# Display.net
KiCad netlist of a schematic drawn in Altium Designer
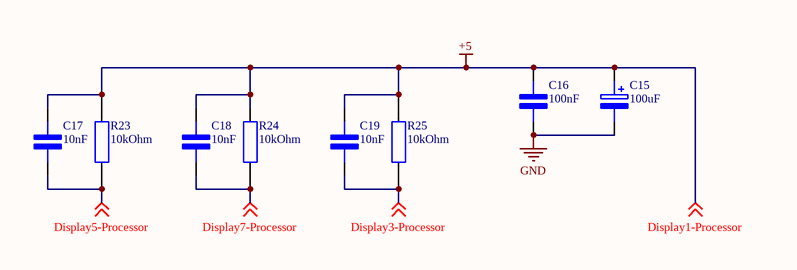
[diagram p0: Display.SchDoc]

(export (version "E")
  (design (tool "Eeschema 10.0.6"))
  (components
    (comp (ref "C15")
      (value "100uF")
      (footprint "PcbLib1:100uF capacitor")
      (description "Capacitor Polarised")
      (fields (field (name "MANUFACTURER_PART_NUMBER") "ESK107M050AG3EA"))
      (libsource (lib "Schlib1") (part "100uF"))
    )
    (comp (ref "C16")
      (value "100nF")
      (footprint "5mm lead spacing capacitor")
      (description "Capacitor")
      (fields (field (name "MANUFACTURER_PART_NUMBER") "UVR1H472MRD"))
      (libsource (lib "Schlib1") (part "100nF"))
    )
    (comp (ref "C17")
      (value "10nF")
      (footprint "5mm lead spacing capacitor")
      (description "Capacitor")
      (fields (field (name "MANUFACTURER_PART_NUMBER") "UVR1H472MRD"))
      (libsource (lib "Schlib1") (part "10nF"))
    )
    (comp (ref "C18")
      (value "10nF")
      (footprint "5mm lead spacing capacitor")
      (description "Capacitor")
      (fields (field (name "MANUFACTURER_PART_NUMBER") "UVR1H472MRD"))
      (libsource (lib "Schlib1") (part "10nF"))
    )
    (comp (ref "C19")
      (value "10nF")
      (footprint "5mm lead spacing capacitor")
      (description "Capacitor")
      (fields (field (name "MANUFACTURER_PART_NUMBER") "UVR1H472MRD"))
      (libsource (lib "Schlib1") (part "10nF"))
    )
    (comp (ref "R23")
      (value "10kOhm")
      (footprint "resistor")
      (description "Resistor")
      (fields (field (name "MANUFACTURER_PART_NUMBER") "CFR-25JT-52-10K"))
      (libsource (lib "Schlib1") (part "10kOhm"))
    )
    (comp (ref "R24")
      (value "10kOhm")
      (footprint "resistor")
      (description "Resistor")
      (fields (field (name "MANUFACTURER_PART_NUMBER") "CFR-25JT-52-10K"))
      (libsource (lib "Schlib1") (part "10kOhm"))
    )
    (comp (ref "R25")
      (value "10kOhm")
      (footprint "resistor")
      (description "Resistor")
      (fields (field (name "MANUFACTURER_PART_NUMBER") "CFR-25JT-52-10K"))
      (libsource (lib "Schlib1") (part "10kOhm"))
    )
  )
  (nets
    (net (code "1") (name "+5") (class "Default")
      (node (ref "C15") (pin "1") (pinfunction "+_1") (pintype "passive"))
      (node (ref "C16") (pin "2") (pinfunction "-_2") (pintype "passive"))
      (node (ref "C17") (pin "2") (pinfunction "-_2") (pintype "passive"))
      (node (ref "C18") (pin "2") (pinfunction "-_2") (pintype "passive"))
      (node (ref "C19") (pin "2") (pinfunction "-_2") (pintype "passive"))
      (node (ref "R23") (pin "2") (pinfunction "2_2") (pintype "passive"))
      (node (ref "R24") (pin "2") (pinfunction "2_2") (pintype "passive"))
      (node (ref "R25") (pin "2") (pinfunction "2_2") (pintype "passive"))
    )
    (net (code "2") (name "Display3-Processor") (class "Default")
      (node (ref "C19") (pin "1") (pinfunction "+_1") (pintype "passive"))
      (node (ref "R25") (pin "1") (pinfunction "1_1") (pintype "passive"))
    )
    (net (code "3") (name "Display5-Processor") (class "Default")
      (node (ref "C17") (pin "1") (pinfunction "+_1") (pintype "passive"))
      (node (ref "R23") (pin "1") (pinfunction "1_1") (pintype "passive"))
    )
    (net (code "4") (name "Display7-Processor") (class "Default")
      (node (ref "C18") (pin "1") (pinfunction "+_1") (pintype "passive"))
      (node (ref "R24") (pin "1") (pinfunction "1_1") (pintype "passive"))
    )
    (net (code "5") (name "GND") (class "Default")
      (node (ref "C15") (pin "2") (pinfunction "-_2") (pintype "passive"))
      (node (ref "C16") (pin "1") (pinfunction "+_1") (pintype "passive"))
    )
  )
)
